# TurntableStrobe.net
KiCad netlist of a schematic drawn in EAGLE
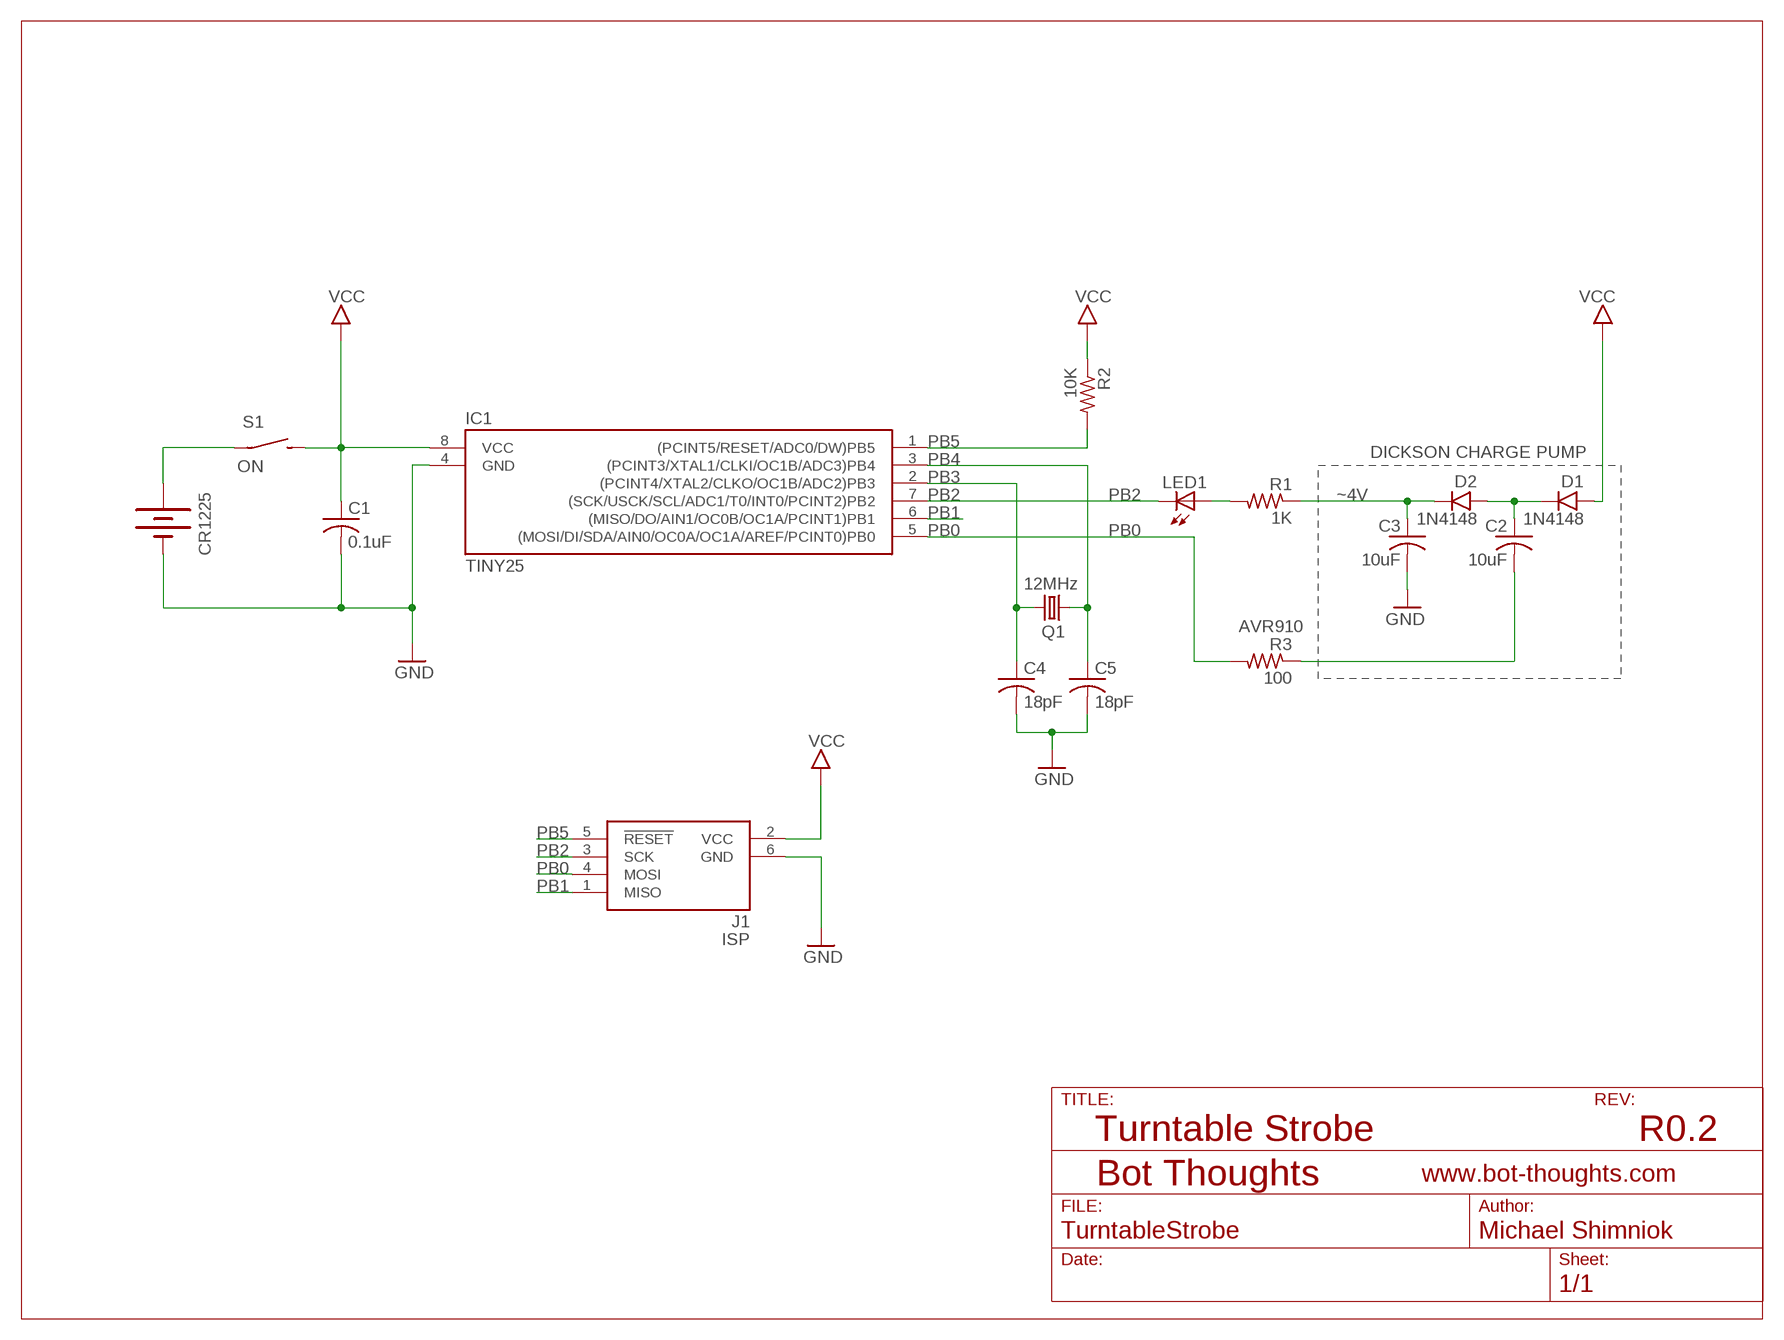
[diagram p0: schematic, sheet 1]

(export (version "E")
  (design (tool "Eeschema 10.0.6"))
  (components
    (comp (ref "C1")
      (value "0.1uF")
      (footprint "eagle-import:C0603")
      (libsource (lib "eagle-import") (part "C-USC0603"))
    )
    (comp (ref "C2")
      (value "10uF")
      (footprint "eagle-import:C0603")
      (libsource (lib "eagle-import") (part "C-USC0603"))
    )
    (comp (ref "C3")
      (value "10uF")
      (footprint "eagle-import:C0603")
      (libsource (lib "eagle-import") (part "C-USC0603"))
    )
    (comp (ref "C4")
      (value "18pF")
      (footprint "eagle-import:C0603")
      (libsource (lib "eagle-import") (part "C-USC0603"))
    )
    (comp (ref "C5")
      (value "18pF")
      (footprint "eagle-import:C0603")
      (libsource (lib "eagle-import") (part "C-USC0603"))
    )
    (comp (ref "CR1225")
      (value "BATTERY12PTH")
      (footprint "eagle-import:BATTCON_12MM_PTH")
      (libsource (lib "eagle-import") (part "BATTERY12PTH"))
    )
    (comp (ref "D1")
      (value "1N4148")
      (footprint "eagle-import:SOD-323")
      (libsource (lib "eagle-import") (part "DIODE_SOD323"))
    )
    (comp (ref "D2")
      (value "1N4148")
      (footprint "eagle-import:SOD-323")
      (libsource (lib "eagle-import") (part "DIODE_SOD323"))
    )
    (comp (ref "IC1")
      (value "TINY25")
      (footprint "eagle-import:SOIC8N")
      (libsource (lib "eagle-import") (part "TINY25/45/85-20SSU"))
    )
    (comp (ref "J1")
      (value "ISP")
      (footprint "eagle-import:2X3_TP")
      (libsource (lib "eagle-import") (part "AVRISP6_TP"))
    )
    (comp (ref "LED1")
      (value "LED5MMRA")
      (footprint "eagle-import:LED5MMRA")
      (libsource (lib "eagle-import") (part "LED5MMRA"))
    )
    (comp (ref "Q1")
      (value "12MHz")
      (footprint "eagle-import:NDK_2PAD_5X3")
      (libsource (lib "eagle-import") (part "CRYSTALNDK5X3"))
    )
    (comp (ref "R1")
      (value "1K")
      (footprint "eagle-import:R0603")
      (libsource (lib "eagle-import") (part "R-US_R0603"))
    )
    (comp (ref "R2")
      (value "10K")
      (footprint "eagle-import:R0603")
      (libsource (lib "eagle-import") (part "R-US_R0603"))
    )
    (comp (ref "R3")
      (value "100")
      (footprint "eagle-import:R0603")
      (libsource (lib "eagle-import") (part "R-US_R0603"))
    )
    (comp (ref "S1")
      (value "ON")
      (footprint "eagle-import:6MMTACTILE_RECT")
      (libsource (lib "eagle-import") (part "SPST_TAC_RECT1"))
    )
  )
  (nets
    (net (code "1") (name "/PB0") (class "Default")
      (node (ref "IC1") (pin "5") (pinfunction "(MOSI/DI/SDA/AIN0/OC0A/OC1A/AREF/PCINT0)PB0_5") (pintype "bidirectional"))
      (node (ref "J1") (pin "4") (pinfunction "MOSI_4") (pintype "output"))
      (node (ref "R3") (pin "2") (pinfunction "2_2") (pintype "passive"))
    )
    (net (code "2") (name "/PB1") (class "Default")
      (node (ref "IC1") (pin "6") (pinfunction "(MISO/DO/AIN1/OC0B/OC1A/PCINT1)PB1_6") (pintype "bidirectional"))
      (node (ref "J1") (pin "1") (pinfunction "MISO_1") (pintype "input"))
    )
    (net (code "3") (name "/PB2") (class "Default")
      (node (ref "IC1") (pin "7") (pinfunction "(SCK/USCK/SCL/ADC1/T0/INT0/PCINT2)PB2_7") (pintype "bidirectional"))
      (node (ref "J1") (pin "3") (pinfunction "SCK_3") (pintype "output"))
      (node (ref "LED1") (pin "C") (pinfunction "C_C") (pintype "passive"))
    )
    (net (code "4") (name "/PB3") (class "Default")
      (node (ref "C4") (pin "1") (pinfunction "1_1") (pintype "passive"))
      (node (ref "IC1") (pin "2") (pinfunction "(PCINT4/XTAL2/CLKO/OC1B/ADC2)PB3_2") (pintype "bidirectional"))
      (node (ref "Q1") (pin "P$2") (pinfunction "2_P$2") (pintype "passive"))
    )
    (net (code "5") (name "/PB4") (class "Default")
      (node (ref "C5") (pin "1") (pinfunction "1_1") (pintype "passive"))
      (node (ref "IC1") (pin "3") (pinfunction "(PCINT3/XTAL1/CLKI/OC1B/ADC3)PB4_3") (pintype "bidirectional"))
      (node (ref "Q1") (pin "P$1") (pinfunction "1_P$1") (pintype "passive"))
    )
    (net (code "6") (name "/PB5") (class "Default")
      (node (ref "IC1") (pin "1") (pinfunction "(PCINT5/RESET/ADC0/DW)PB5_1") (pintype "bidirectional"))
      (node (ref "J1") (pin "5") (pinfunction "~{RESET}_5") (pintype "output"))
      (node (ref "R2") (pin "2") (pinfunction "2_2") (pintype "passive"))
    )
    (net (code "7") (name "GND") (class "Default")
      (node (ref "C1") (pin "2") (pinfunction "2_2") (pintype "passive"))
      (node (ref "C3") (pin "2") (pinfunction "2_2") (pintype "passive"))
      (node (ref "C4") (pin "2") (pinfunction "2_2") (pintype "passive"))
      (node (ref "C5") (pin "2") (pinfunction "2_2") (pintype "passive"))
      (node (ref "CR1225") (pin "GND") (pinfunction "-_GND") (pintype "power_in"))
      (node (ref "IC1") (pin "4") (pinfunction "GND_4") (pintype "power_in"))
      (node (ref "J1") (pin "6") (pinfunction "GND_6") (pintype "power_in"))
    )
    (net (code "8") (name "Net-(C2-Pad1)") (class "Default")
      (node (ref "C2") (pin "1") (pinfunction "1_1") (pintype "passive"))
      (node (ref "D1") (pin "C") (pinfunction "C_C") (pintype "passive"))
      (node (ref "D2") (pin "A") (pinfunction "A_A") (pintype "passive"))
    )
    (net (code "9") (name "Net-(C2-Pad2)") (class "Default")
      (node (ref "C2") (pin "2") (pinfunction "2_2") (pintype "passive"))
      (node (ref "R3") (pin "1") (pinfunction "1_1") (pintype "passive"))
    )
    (net (code "10") (name "Net-(C3-Pad1)") (class "Default")
      (node (ref "C3") (pin "1") (pinfunction "1_1") (pintype "passive"))
      (node (ref "D2") (pin "C") (pinfunction "C_C") (pintype "passive"))
      (node (ref "R1") (pin "1") (pinfunction "1_1") (pintype "passive"))
    )
    (net (code "11") (name "Net-(CR1225-+)") (class "Default")
      (node (ref "CR1225") (pin "VCC@1") (pinfunction "+_VCC@1") (pintype "power_in"))
      (node (ref "S1") (pin "P$1") (pinfunction "P_P$1") (pintype "passive"))
    )
    (net (code "12") (name "Net-(LED1-PadA)") (class "Default")
      (node (ref "LED1") (pin "A") (pinfunction "A_A") (pintype "passive"))
      (node (ref "R1") (pin "2") (pinfunction "2_2") (pintype "passive"))
    )
    (net (code "13") (name "VCC") (class "Default")
      (node (ref "C1") (pin "1") (pinfunction "1_1") (pintype "passive"))
      (node (ref "D1") (pin "A") (pinfunction "A_A") (pintype "passive"))
      (node (ref "IC1") (pin "8") (pinfunction "VCC_8") (pintype "power_in"))
      (node (ref "J1") (pin "2") (pinfunction "VCC_2") (pintype "power_in"))
      (node (ref "R2") (pin "1") (pinfunction "1_1") (pintype "passive"))
      (node (ref "S1") (pin "P$2") (pinfunction "S_P$2") (pintype "passive"))
    )
  )
)
